# B2_0-_-2_0-stm32c8t6_-24_10_17.net
KiCad netlist of a schematic drawn in Altium Designer
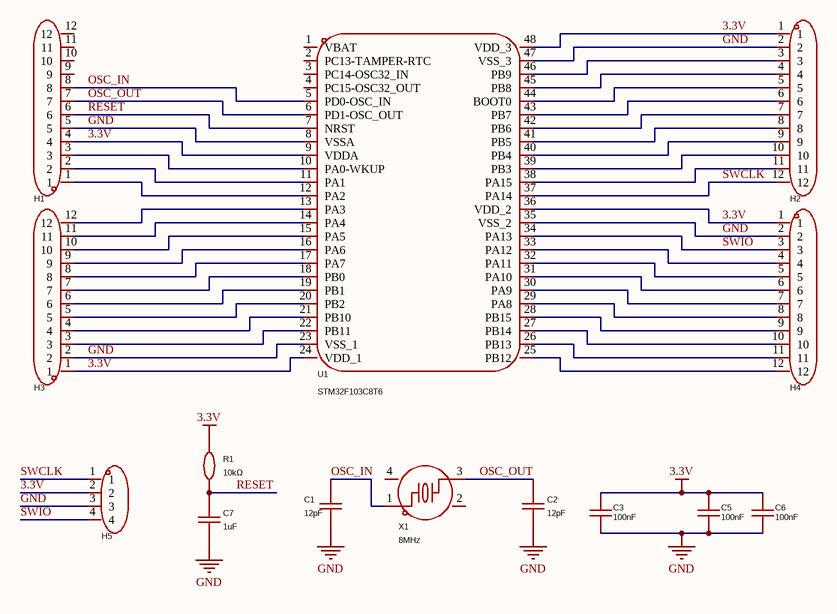
[diagram p0: B2.0-主板-2.0-stm32c8t6最小系统板-24.10.17.SchDoc]

(export (version "E")
  (design (tool "Eeschema 10.0.6"))
  (components
    (comp (ref "C1")
      (value "12pF")
      (footprint "C0603")
      (fields
        (field (name "MANUFACTURER") "YAGEO(国巨)")
        (field (name "MANUFACTURER PART") "CC0603FRNPO9BN120")
        (field (name "TOLERANCE") "±1%")
      )
      (libsource (lib "电容") (part "CC0603FRNPO9BN120"))
    )
    (comp (ref "C2")
      (value "12pF")
      (footprint "C0603")
      (fields
        (field (name "MANUFACTURER") "YAGEO(国巨)")
        (field (name "MANUFACTURER PART") "CC0603FRNPO9BN120")
        (field (name "TOLERANCE") "±1%")
      )
      (libsource (lib "电容") (part "CC0603FRNPO9BN120"))
    )
    (comp (ref "C3")
      (value "100nF")
      (footprint "C0603")
      (fields
        (field (name "MANUFACTURER") "FH(风华)")
        (field (name "MANUFACTURER PART") "0603B104K500NT")
        (field (name "TOLERANCE") "±10%")
      )
      (libsource (lib "电容") (part "0603B104K500NT"))
    )
    (comp (ref "C5")
      (value "100nF")
      (footprint "C0603")
      (fields
        (field (name "MANUFACTURER") "FH(风华)")
        (field (name "MANUFACTURER PART") "0603B104K500NT")
        (field (name "TOLERANCE") "±10%")
      )
      (libsource (lib "电容") (part "0603B104K500NT"))
    )
    (comp (ref "C6")
      (value "100nF")
      (footprint "C0603")
      (fields
        (field (name "MANUFACTURER") "FH(风华)")
        (field (name "MANUFACTURER PART") "0603B104K500NT")
        (field (name "TOLERANCE") "±10%")
      )
      (libsource (lib "电容") (part "0603B104K500NT"))
    )
    (comp (ref "C7")
      (value "1uF")
      (footprint "C0603")
      (fields
        (field (name "MANUFACTURER") "YAGEO(国巨)")
        (field (name "MANUFACTURER PART") "CC0603KRX7R9BB105")
        (field (name "TOLERANCE") "±10%")
      )
      (libsource (lib "电容") (part "CC0603KRX7R9BB105"))
    )
    (comp (ref "H1")
      (value "PZ254V-11-12P")
      (footprint "HDR-TH_12P-P2.54-V-M")
      (fields (field (name "MANUFACTURER") "XFCN(兴飞)"))
      (libsource (lib "连接器") (part "PZ254V-11-12P"))
    )
    (comp (ref "H2")
      (value "PZ254V-11-12P")
      (footprint "HDR-TH_12P-P2.54-V-M")
      (fields (field (name "MANUFACTURER") "XFCN(兴飞)"))
      (libsource (lib "连接器") (part "PZ254V-11-12P"))
    )
    (comp (ref "H3")
      (value "PZ254V-11-12P")
      (footprint "HDR-TH_12P-P2.54-V-M")
      (fields (field (name "MANUFACTURER") "XFCN(兴飞)"))
      (libsource (lib "连接器") (part "PZ254V-11-12P"))
    )
    (comp (ref "H4")
      (value "PZ254V-11-12P")
      (footprint "HDR-TH_12P-P2.54-V-M")
      (fields (field (name "MANUFACTURER") "XFCN(兴飞)"))
      (libsource (lib "连接器") (part "PZ254V-11-12P"))
    )
    (comp (ref "H5")
      (value "PZ254V-11-04P")
      (footprint "HDR-TH_4P-P2.54-V-M")
      (fields (field (name "MANUFACTURER") "XFCN(兴飞)"))
      (libsource (lib "连接器") (part "PZ254V-11-04P"))
    )
    (comp (ref "R1")
      (value "10kΩ")
      (footprint "R0805")
      (fields
        (field (name "MANUFACTURER") "UNI-ROYAL(厚声)")
        (field (name "MANUFACTURER PART") "0805W8J0103T5E")
        (field (name "TOLERANCE") "±5%")
      )
      (libsource (lib "电阻") (part "0805W8J0103T5E"))
    )
    (comp (ref "U1")
      (value "STM32F103C8T6")
      (footprint "LQFP-48_L7.0-W7.0-P0.50-LS9.0-BL")
      (fields (field (name "MANUFACTURER") "ST(意法半导体)"))
      (libsource (lib "IC") (part "STM32F103C8T6"))
    )
    (comp (ref "X1")
      (value "8MHz")
      (footprint "OSC-SMD_4P-L3.2-W2.5-BL")
      (fields (field (name "MANUFACTURER") "YXC(扬兴晶振)") (field (name "MANUFACTURER PART") "X32258MOB4SI"))
      (libsource (lib "晶振") (part "X32258MOB4SI"))
    )
  )
  (nets
    (net (code "1") (name "/OSC_IN") (class "Default")
      (node (ref "C1") (pin "2") (pinfunction "2_2") (pintype "passive"))
      (node (ref "H1") (pin "8") (pinfunction "8_8") (pintype "passive"))
      (node (ref "U1") (pin "5") (pinfunction "PD0-OSC_IN_5") (pintype "passive"))
      (node (ref "X1") (pin "1") (pinfunction "1_1") (pintype "passive"))
    )
    (net (code "2") (name "/OSC_OUT") (class "Default")
      (node (ref "C2") (pin "2") (pinfunction "2_2") (pintype "passive"))
      (node (ref "H1") (pin "7") (pinfunction "7_7") (pintype "passive"))
      (node (ref "U1") (pin "6") (pinfunction "PD1-OSC_OUT_6") (pintype "passive"))
      (node (ref "X1") (pin "3") (pinfunction "3_3") (pintype "passive"))
    )
    (net (code "3") (name "/RESET") (class "Default")
      (node (ref "C7") (pin "2") (pinfunction "2_2") (pintype "passive"))
      (node (ref "H1") (pin "6") (pinfunction "6_6") (pintype "passive"))
      (node (ref "R1") (pin "1") (pinfunction "1_1") (pintype "passive"))
      (node (ref "U1") (pin "7") (pinfunction "NRST_7") (pintype "passive"))
    )
    (net (code "4") (name "/SWCLK") (class "Default")
      (node (ref "H2") (pin "12") (pinfunction "12_12") (pintype "passive"))
      (node (ref "H5") (pin "1") (pinfunction "1_1") (pintype "passive"))
      (node (ref "U1") (pin "37") (pinfunction "PA14_37") (pintype "passive"))
    )
    (net (code "5") (name "/SWIO") (class "Default")
      (node (ref "H4") (pin "3") (pinfunction "3_3") (pintype "passive"))
      (node (ref "H5") (pin "4") (pinfunction "4_4") (pintype "passive"))
      (node (ref "U1") (pin "34") (pinfunction "PA13_34") (pintype "passive"))
    )
    (net (code "6") (name "3.3V") (class "Default")
      (node (ref "C3") (pin "2") (pinfunction "2_2") (pintype "passive"))
      (node (ref "C5") (pin "2") (pinfunction "2_2") (pintype "passive"))
      (node (ref "C6") (pin "2") (pinfunction "2_2") (pintype "passive"))
      (node (ref "H1") (pin "4") (pinfunction "4_4") (pintype "passive"))
      (node (ref "H2") (pin "1") (pinfunction "1_1") (pintype "passive"))
      (node (ref "H3") (pin "1") (pinfunction "1_1") (pintype "passive"))
      (node (ref "H4") (pin "1") (pinfunction "1_1") (pintype "passive"))
      (node (ref "H5") (pin "2") (pinfunction "2_2") (pintype "passive"))
      (node (ref "R1") (pin "2") (pinfunction "2_2") (pintype "passive"))
      (node (ref "U1") (pin "24") (pinfunction "VDD_1_24") (pintype "passive"))
      (node (ref "U1") (pin "36") (pinfunction "VDD_2_36") (pintype "passive"))
      (node (ref "U1") (pin "48") (pinfunction "VDD_3_48") (pintype "passive"))
      (node (ref "U1") (pin "9") (pinfunction "VDDA_9") (pintype "passive"))
    )
    (net (code "7") (name "GND") (class "Default")
      (node (ref "C1") (pin "1") (pinfunction "1_1") (pintype "passive"))
      (node (ref "C2") (pin "1") (pinfunction "1_1") (pintype "passive"))
      (node (ref "C3") (pin "1") (pinfunction "1_1") (pintype "passive"))
      (node (ref "C5") (pin "1") (pinfunction "1_1") (pintype "passive"))
      (node (ref "C6") (pin "1") (pinfunction "1_1") (pintype "passive"))
      (node (ref "C7") (pin "1") (pinfunction "1_1") (pintype "passive"))
      (node (ref "H1") (pin "5") (pinfunction "5_5") (pintype "passive"))
      (node (ref "H2") (pin "2") (pinfunction "2_2") (pintype "passive"))
      (node (ref "H3") (pin "2") (pinfunction "2_2") (pintype "passive"))
      (node (ref "H4") (pin "2") (pinfunction "2_2") (pintype "passive"))
      (node (ref "H5") (pin "3") (pinfunction "3_3") (pintype "passive"))
      (node (ref "U1") (pin "23") (pinfunction "VSS_1_23") (pintype "passive"))
      (node (ref "U1") (pin "35") (pinfunction "VSS_2_35") (pintype "passive"))
      (node (ref "U1") (pin "47") (pinfunction "VSS_3_47") (pintype "passive"))
      (node (ref "U1") (pin "8") (pinfunction "VSSA_8") (pintype "passive"))
    )
    (net (code "8") (name "Net-(U1-BOOT0)") (class "Default")
      (node (ref "H2") (pin "5") (pinfunction "5_5") (pintype "passive"))
      (node (ref "U1") (pin "44") (pinfunction "BOOT0_44") (pintype "passive"))
    )
    (net (code "9") (name "Net-(U1-PA0-WKUP)") (class "Default")
      (node (ref "H1") (pin "3") (pinfunction "3_3") (pintype "passive"))
      (node (ref "U1") (pin "10") (pinfunction "PA0-WKUP_10") (pintype "passive"))
    )
    (net (code "10") (name "Net-(U1-PA1)") (class "Default")
      (node (ref "H1") (pin "2") (pinfunction "2_2") (pintype "passive"))
      (node (ref "U1") (pin "11") (pinfunction "PA1_11") (pintype "passive"))
    )
    (net (code "11") (name "Net-(U1-PA2)") (class "Default")
      (node (ref "H1") (pin "1") (pinfunction "1_1") (pintype "passive"))
      (node (ref "U1") (pin "12") (pinfunction "PA2_12") (pintype "passive"))
    )
    (net (code "12") (name "Net-(U1-PA3)") (class "Default")
      (node (ref "H3") (pin "12") (pinfunction "12_12") (pintype "passive"))
      (node (ref "U1") (pin "13") (pinfunction "PA3_13") (pintype "passive"))
    )
    (net (code "13") (name "Net-(U1-PA4)") (class "Default")
      (node (ref "H3") (pin "11") (pinfunction "11_11") (pintype "passive"))
      (node (ref "U1") (pin "14") (pinfunction "PA4_14") (pintype "passive"))
    )
    (net (code "14") (name "Net-(U1-PA5)") (class "Default")
      (node (ref "H3") (pin "10") (pinfunction "10_10") (pintype "passive"))
      (node (ref "U1") (pin "15") (pinfunction "PA5_15") (pintype "passive"))
    )
    (net (code "15") (name "Net-(U1-PA6)") (class "Default")
      (node (ref "H3") (pin "9") (pinfunction "9_9") (pintype "passive"))
      (node (ref "U1") (pin "16") (pinfunction "PA6_16") (pintype "passive"))
    )
    (net (code "16") (name "Net-(U1-PA7)") (class "Default")
      (node (ref "H3") (pin "8") (pinfunction "8_8") (pintype "passive"))
      (node (ref "U1") (pin "17") (pinfunction "PA7_17") (pintype "passive"))
    )
    (net (code "17") (name "Net-(U1-PA8)") (class "Default")
      (node (ref "H4") (pin "8") (pinfunction "8_8") (pintype "passive"))
      (node (ref "U1") (pin "29") (pinfunction "PA8_29") (pintype "passive"))
    )
    (net (code "18") (name "Net-(U1-PA9)") (class "Default")
      (node (ref "H4") (pin "7") (pinfunction "7_7") (pintype "passive"))
      (node (ref "U1") (pin "30") (pinfunction "PA9_30") (pintype "passive"))
    )
    (net (code "19") (name "Net-(U1-PA10)") (class "Default")
      (node (ref "H4") (pin "6") (pinfunction "6_6") (pintype "passive"))
      (node (ref "U1") (pin "31") (pinfunction "PA10_31") (pintype "passive"))
    )
    (net (code "20") (name "Net-(U1-PA11)") (class "Default")
      (node (ref "H4") (pin "5") (pinfunction "5_5") (pintype "passive"))
      (node (ref "U1") (pin "32") (pinfunction "PA11_32") (pintype "passive"))
    )
    (net (code "21") (name "Net-(U1-PA12)") (class "Default")
      (node (ref "H4") (pin "4") (pinfunction "4_4") (pintype "passive"))
      (node (ref "U1") (pin "33") (pinfunction "PA12_33") (pintype "passive"))
    )
    (net (code "22") (name "Net-(U1-PA15)") (class "Default")
      (node (ref "H2") (pin "11") (pinfunction "11_11") (pintype "passive"))
      (node (ref "U1") (pin "38") (pinfunction "PA15_38") (pintype "passive"))
    )
    (net (code "23") (name "Net-(U1-PB0)") (class "Default")
      (node (ref "H3") (pin "7") (pinfunction "7_7") (pintype "passive"))
      (node (ref "U1") (pin "18") (pinfunction "PB0_18") (pintype "passive"))
    )
    (net (code "24") (name "Net-(U1-PB1)") (class "Default")
      (node (ref "H3") (pin "6") (pinfunction "6_6") (pintype "passive"))
      (node (ref "U1") (pin "19") (pinfunction "PB1_19") (pintype "passive"))
    )
    (net (code "25") (name "Net-(U1-PB2)") (class "Default")
      (node (ref "H3") (pin "5") (pinfunction "5_5") (pintype "passive"))
      (node (ref "U1") (pin "20") (pinfunction "PB2_20") (pintype "passive"))
    )
    (net (code "26") (name "Net-(U1-PB3)") (class "Default")
      (node (ref "H2") (pin "10") (pinfunction "10_10") (pintype "passive"))
      (node (ref "U1") (pin "39") (pinfunction "PB3_39") (pintype "passive"))
    )
    (net (code "27") (name "Net-(U1-PB4)") (class "Default")
      (node (ref "H2") (pin "9") (pinfunction "9_9") (pintype "passive"))
      (node (ref "U1") (pin "40") (pinfunction "PB4_40") (pintype "passive"))
    )
    (net (code "28") (name "Net-(U1-PB5)") (class "Default")
      (node (ref "H2") (pin "8") (pinfunction "8_8") (pintype "passive"))
      (node (ref "U1") (pin "41") (pinfunction "PB5_41") (pintype "passive"))
    )
    (net (code "29") (name "Net-(U1-PB6)") (class "Default")
      (node (ref "H2") (pin "7") (pinfunction "7_7") (pintype "passive"))
      (node (ref "U1") (pin "42") (pinfunction "PB6_42") (pintype "passive"))
    )
    (net (code "30") (name "Net-(U1-PB7)") (class "Default")
      (node (ref "H2") (pin "6") (pinfunction "6_6") (pintype "passive"))
      (node (ref "U1") (pin "43") (pinfunction "PB7_43") (pintype "passive"))
    )
    (net (code "31") (name "Net-(U1-PB8)") (class "Default")
      (node (ref "H2") (pin "4") (pinfunction "4_4") (pintype "passive"))
      (node (ref "U1") (pin "45") (pinfunction "PB8_45") (pintype "passive"))
    )
    (net (code "32") (name "Net-(U1-PB9)") (class "Default")
      (node (ref "H2") (pin "3") (pinfunction "3_3") (pintype "passive"))
      (node (ref "U1") (pin "46") (pinfunction "PB9_46") (pintype "passive"))
    )
    (net (code "33") (name "Net-(U1-PB10)") (class "Default")
      (node (ref "H3") (pin "4") (pinfunction "4_4") (pintype "passive"))
      (node (ref "U1") (pin "21") (pinfunction "PB10_21") (pintype "passive"))
    )
    (net (code "34") (name "Net-(U1-PB11)") (class "Default")
      (node (ref "H3") (pin "3") (pinfunction "3_3") (pintype "passive"))
      (node (ref "U1") (pin "22") (pinfunction "PB11_22") (pintype "passive"))
    )
    (net (code "35") (name "Net-(U1-PB12)") (class "Default")
      (node (ref "H4") (pin "12") (pinfunction "12_12") (pintype "passive"))
      (node (ref "U1") (pin "25") (pinfunction "PB12_25") (pintype "passive"))
    )
    (net (code "36") (name "Net-(U1-PB13)") (class "Default")
      (node (ref "H4") (pin "11") (pinfunction "11_11") (pintype "passive"))
      (node (ref "U1") (pin "26") (pinfunction "PB13_26") (pintype "passive"))
    )
    (net (code "37") (name "Net-(U1-PB14)") (class "Default")
      (node (ref "H4") (pin "10") (pinfunction "10_10") (pintype "passive"))
      (node (ref "U1") (pin "27") (pinfunction "PB14_27") (pintype "passive"))
    )
    (net (code "38") (name "Net-(U1-PB15)") (class "Default")
      (node (ref "H4") (pin "9") (pinfunction "9_9") (pintype "passive"))
      (node (ref "U1") (pin "28") (pinfunction "PB15_28") (pintype "passive"))
    )
    (net (code "39") (name "unconnected-(H1-Pad9)") (class "Default")
      (node (ref "H1") (pin "9") (pinfunction "9_9") (pintype "passive"))
    )
    (net (code "40") (name "unconnected-(H1-Pad10)") (class "Default")
      (node (ref "H1") (pin "10") (pinfunction "10_10") (pintype "passive"))
    )
    (net (code "41") (name "unconnected-(H1-Pad11)") (class "Default")
      (node (ref "H1") (pin "11") (pinfunction "11_11") (pintype "passive"))
    )
    (net (code "42") (name "unconnected-(H1-Pad12)") (class "Default")
      (node (ref "H1") (pin "12") (pinfunction "12_12") (pintype "passive"))
    )
    (net (code "43") (name "unconnected-(U1-PC13-TAMPER-RTC-Pad2)") (class "Default")
      (node (ref "U1") (pin "2") (pinfunction "PC13-TAMPER-RTC_2") (pintype "passive"))
    )
    (net (code "44") (name "unconnected-(U1-PC14-OSC32_IN-Pad3)") (class "Default")
      (node (ref "U1") (pin "3") (pinfunction "PC14-OSC32_IN_3") (pintype "passive"))
    )
    (net (code "45") (name "unconnected-(U1-PC15-OSC32_OUT-Pad4)") (class "Default")
      (node (ref "U1") (pin "4") (pinfunction "PC15-OSC32_OUT_4") (pintype "passive"))
    )
    (net (code "46") (name "unconnected-(U1-VBAT-Pad1)") (class "Default")
      (node (ref "U1") (pin "1") (pinfunction "VBAT_1") (pintype "passive"))
    )
    (net (code "47") (name "unconnected-(X1-GND-Pad2)") (class "Default")
      (node (ref "X1") (pin "2") (pinfunction "GND_2") (pintype "passive"))
    )
    (net (code "48") (name "unconnected-(X1-GND-Pad4)") (class "Default")
      (node (ref "X1") (pin "4") (pinfunction "GND_4") (pintype "passive"))
    )
  )
)
